# BrushlessMotorController.net
KiCad netlist of a schematic drawn in EAGLE
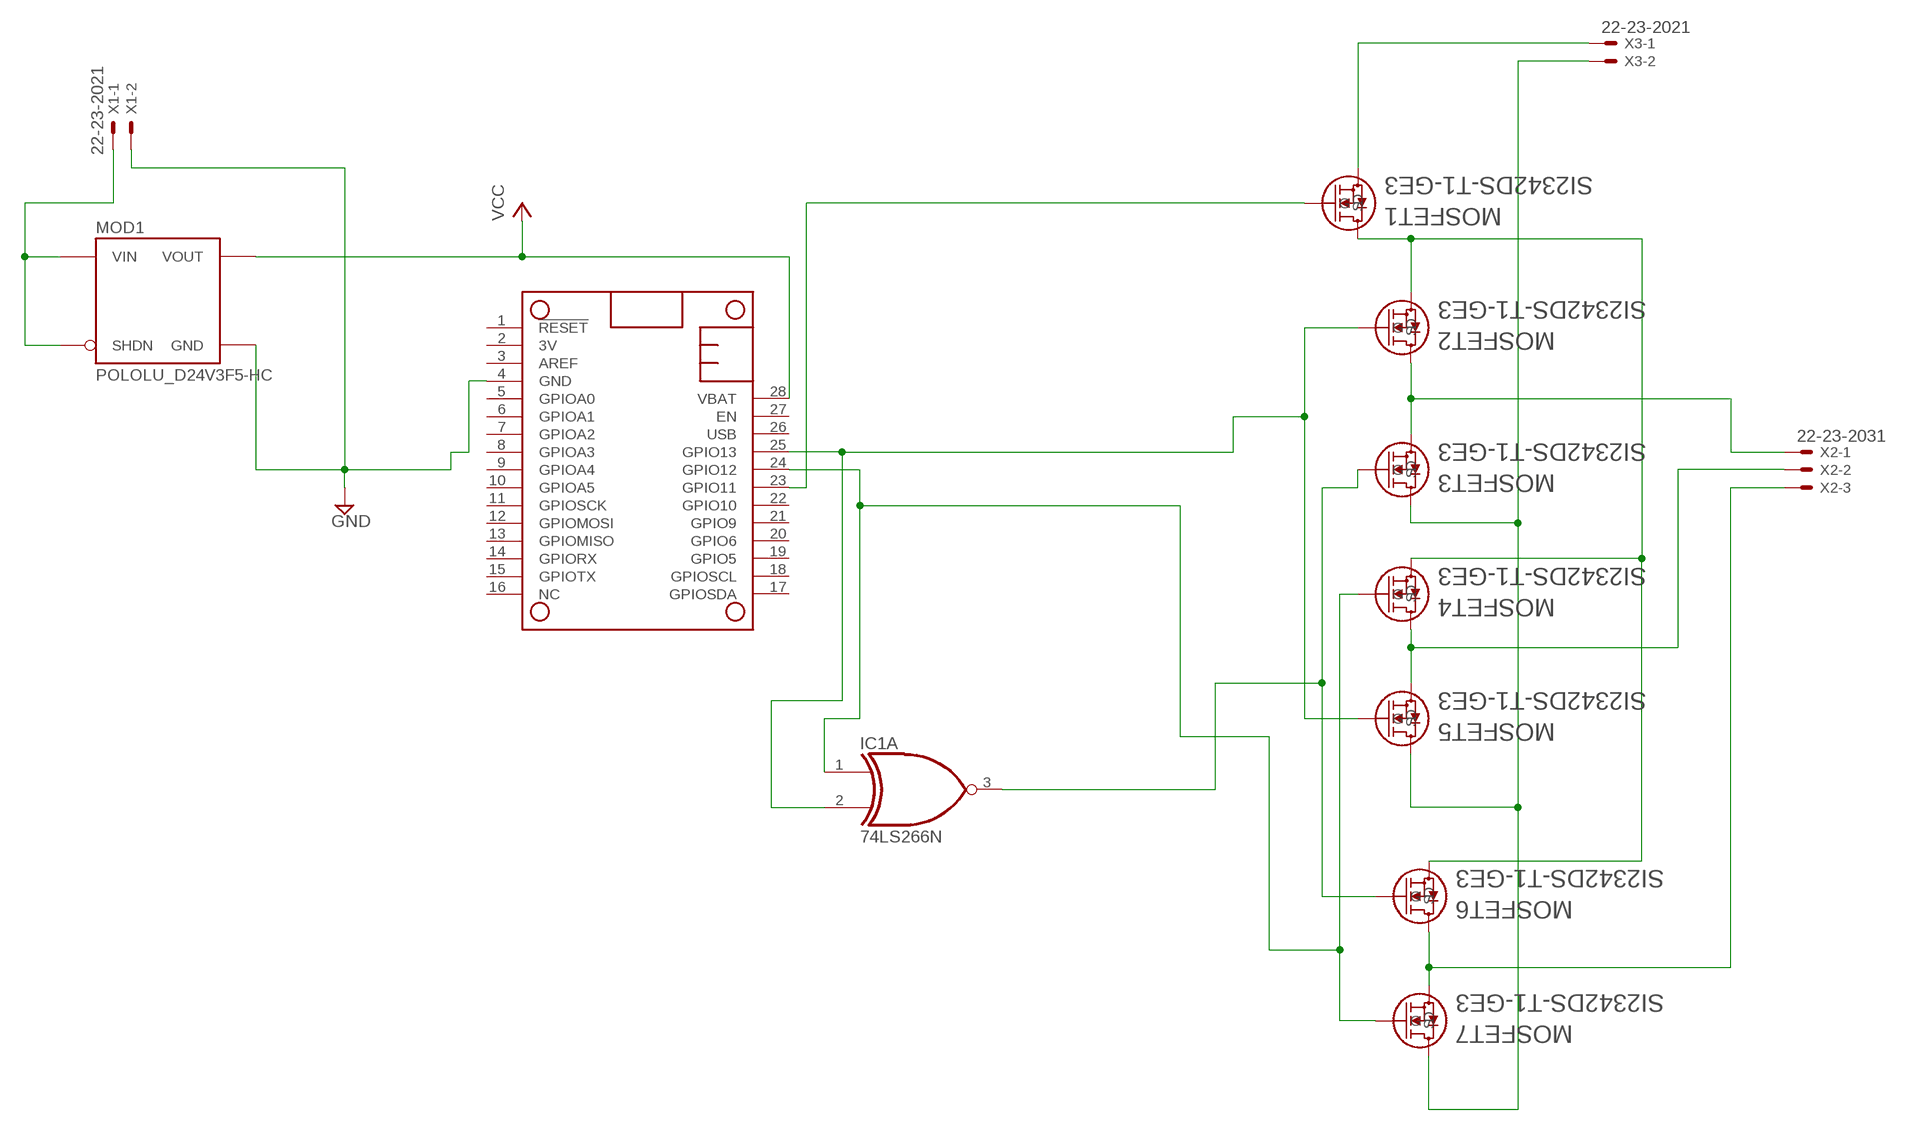
[diagram p0: schematic, sheet 1]

(export (version "E")
  (design (tool "Eeschema 10.0.6"))
  (components
    (comp (ref "IC1")
      (value "74LS266N")
      (footprint "eagle-import:DIL14")
      (libsource (lib "eagle-import") (part "74266NLS"))
    )
    (comp (ref "MOD1")
      (value "POLOLU_D24V3F5-HC")
      (footprint "eagle-import:POLOLU_D24V3F_HC")
      (libsource (lib "eagle-import") (part "POLOLU_D24V3F-HC5"))
    )
    (comp (ref "MOSFET1")
      (value "SI2342DS-T1-GE3")
      (footprint "eagle-import:SOT-23_TO-236_VIS")
      (fields (field (name "COPYRIGHT") "Copyright (C) 2018 Accelerated Designs. All rights reserved"))
      (libsource (lib "eagle-import") (part "SI2342DS-T1-GE3"))
    )
    (comp (ref "MOSFET2")
      (value "SI2342DS-T1-GE3")
      (footprint "eagle-import:SOT-23_TO-236_VIS")
      (fields (field (name "COPYRIGHT") "Copyright (C) 2018 Accelerated Designs. All rights reserved"))
      (libsource (lib "eagle-import") (part "SI2342DS-T1-GE3"))
    )
    (comp (ref "MOSFET3")
      (value "SI2342DS-T1-GE3")
      (footprint "eagle-import:SOT-23_TO-236_VIS")
      (fields (field (name "COPYRIGHT") "Copyright (C) 2018 Accelerated Designs. All rights reserved"))
      (libsource (lib "eagle-import") (part "SI2342DS-T1-GE3"))
    )
    (comp (ref "MOSFET4")
      (value "SI2342DS-T1-GE3")
      (footprint "eagle-import:SOT-23_TO-236_VIS")
      (fields (field (name "COPYRIGHT") "Copyright (C) 2018 Accelerated Designs. All rights reserved"))
      (libsource (lib "eagle-import") (part "SI2342DS-T1-GE3"))
    )
    (comp (ref "MOSFET5")
      (value "SI2342DS-T1-GE3")
      (footprint "eagle-import:SOT-23_TO-236_VIS")
      (fields (field (name "COPYRIGHT") "Copyright (C) 2018 Accelerated Designs. All rights reserved"))
      (libsource (lib "eagle-import") (part "SI2342DS-T1-GE3"))
    )
    (comp (ref "MOSFET6")
      (value "SI2342DS-T1-GE3")
      (footprint "eagle-import:SOT-23_TO-236_VIS")
      (fields (field (name "COPYRIGHT") "Copyright (C) 2018 Accelerated Designs. All rights reserved"))
      (libsource (lib "eagle-import") (part "SI2342DS-T1-GE3"))
    )
    (comp (ref "MOSFET7")
      (value "SI2342DS-T1-GE3")
      (footprint "eagle-import:SOT-23_TO-236_VIS")
      (fields (field (name "COPYRIGHT") "Copyright (C) 2018 Accelerated Designs. All rights reserved"))
      (libsource (lib "eagle-import") (part "SI2342DS-T1-GE3"))
    )
    (comp (ref "MS2")
      (value "FEATHERWING_NODIM")
      (footprint "eagle-import:FEATHERWING_DIM")
      (libsource (lib "eagle-import") (part "FEATHERWING_NODIM"))
    )
    (comp (ref "X1")
      (value "22-23-2021")
      (footprint "eagle-import:22-23-2021")
      (fields (field (name "MF") "MOLEX"))
      (libsource (lib "eagle-import") (part "22-23-2021"))
    )
    (comp (ref "X2")
      (value "22-23-2031")
      (footprint "eagle-import:22-23-2031")
      (fields (field (name "MF") "MOLEX"))
      (libsource (lib "eagle-import") (part "22-23-2031"))
    )
    (comp (ref "X3")
      (value "22-23-2021")
      (footprint "eagle-import:22-23-2021")
      (fields (field (name "MF") "MOLEX"))
      (libsource (lib "eagle-import") (part "22-23-2021"))
    )
  )
  (nets
    (net (code "1") (name "/3V") (class "Default")
      (node (ref "MS2") (pin "2") (pinfunction "3V_2") (pintype "power_in"))
    )
    (net (code "2") (name "/USB") (class "Default")
      (node (ref "MS2") (pin "26") (pinfunction "USB_26") (pintype "power_in"))
    )
    (net (code "3") (name "GND") (class "Default")
      (node (ref "MOD1") (pin "G") (pinfunction "GND_G") (pintype "power_in"))
      (node (ref "MS2") (pin "4") (pinfunction "GND_4") (pintype "power_in"))
      (node (ref "X1") (pin "2") (pinfunction "S_2") (pintype "passive"))
    )
    (net (code "4") (name "Net-(IC1A-I0)") (class "Default")
      (node (ref "IC1") (pin "1") (pinfunction "I0_1") (pintype "input"))
      (node (ref "MOSFET4") (pin "1") (pinfunction "G_1") (pintype "passive"))
      (node (ref "MOSFET7") (pin "1") (pinfunction "G_1") (pintype "passive"))
      (node (ref "MS2") (pin "24") (pinfunction "GPIO12_24") (pintype "bidirectional"))
    )
    (net (code "5") (name "Net-(IC1A-I1)") (class "Default")
      (node (ref "IC1") (pin "2") (pinfunction "I1_2") (pintype "input"))
      (node (ref "MOSFET2") (pin "1") (pinfunction "G_1") (pintype "passive"))
      (node (ref "MOSFET5") (pin "1") (pinfunction "G_1") (pintype "passive"))
      (node (ref "MS2") (pin "25") (pinfunction "GPIO13_25") (pintype "bidirectional"))
    )
    (net (code "6") (name "Net-(IC1A-O)") (class "Default")
      (node (ref "IC1") (pin "3") (pinfunction "O_3") (pintype "open_collector"))
      (node (ref "MOSFET3") (pin "1") (pinfunction "G_1") (pintype "passive"))
      (node (ref "MOSFET6") (pin "1") (pinfunction "G_1") (pintype "passive"))
    )
    (net (code "7") (name "Net-(MOD1-SHDN)") (class "Default")
      (node (ref "MOD1") (pin "I") (pinfunction "VIN_I") (pintype "power_in"))
      (node (ref "MOD1") (pin "S") (pinfunction "SHDN_S") (pintype "input"))
      (node (ref "X1") (pin "1") (pinfunction "S_1") (pintype "passive"))
    )
    (net (code "8") (name "Net-(MOSFET1-D)") (class "Default")
      (node (ref "MOSFET1") (pin "3") (pinfunction "D_3") (pintype "passive"))
      (node (ref "MOSFET2") (pin "2") (pinfunction "S_2") (pintype "passive"))
      (node (ref "MOSFET4") (pin "2") (pinfunction "S_2") (pintype "passive"))
      (node (ref "MOSFET6") (pin "2") (pinfunction "S_2") (pintype "passive"))
    )
    (net (code "9") (name "Net-(MOSFET1-G)") (class "Default")
      (node (ref "MOSFET1") (pin "1") (pinfunction "G_1") (pintype "passive"))
      (node (ref "MS2") (pin "23") (pinfunction "GPIO11_23") (pintype "bidirectional"))
    )
    (net (code "10") (name "Net-(MOSFET1-S)") (class "Default")
      (node (ref "MOSFET1") (pin "2") (pinfunction "S_2") (pintype "passive"))
      (node (ref "X3") (pin "1") (pinfunction "S_1") (pintype "passive"))
    )
    (net (code "11") (name "Net-(MOSFET2-D)") (class "Default")
      (node (ref "MOSFET2") (pin "3") (pinfunction "D_3") (pintype "passive"))
      (node (ref "MOSFET3") (pin "2") (pinfunction "S_2") (pintype "passive"))
      (node (ref "X2") (pin "1") (pinfunction "S_1") (pintype "passive"))
    )
    (net (code "12") (name "Net-(MOSFET3-D)") (class "Default")
      (node (ref "MOSFET3") (pin "3") (pinfunction "D_3") (pintype "passive"))
      (node (ref "MOSFET5") (pin "3") (pinfunction "D_3") (pintype "passive"))
      (node (ref "MOSFET7") (pin "3") (pinfunction "D_3") (pintype "passive"))
      (node (ref "X3") (pin "2") (pinfunction "S_2") (pintype "passive"))
    )
    (net (code "13") (name "Net-(MOSFET4-D)") (class "Default")
      (node (ref "MOSFET4") (pin "3") (pinfunction "D_3") (pintype "passive"))
      (node (ref "MOSFET5") (pin "2") (pinfunction "S_2") (pintype "passive"))
      (node (ref "X2") (pin "2") (pinfunction "S_2") (pintype "passive"))
    )
    (net (code "14") (name "Net-(MOSFET6-D)") (class "Default")
      (node (ref "MOSFET6") (pin "3") (pinfunction "D_3") (pintype "passive"))
      (node (ref "MOSFET7") (pin "2") (pinfunction "S_2") (pintype "passive"))
      (node (ref "X2") (pin "3") (pinfunction "S_3") (pintype "passive"))
    )
    (net (code "15") (name "VCC") (class "Default")
      (node (ref "MOD1") (pin "O") (pinfunction "VOUT_O") (pintype "output"))
      (node (ref "MS2") (pin "28") (pinfunction "VBAT_28") (pintype "power_in"))
    )
    (net (code "16") (name "unconnected-(MS2-AREF-Pad3)") (class "Default")
      (node (ref "MS2") (pin "3") (pinfunction "AREF_3") (pintype "passive"))
    )
    (net (code "17") (name "unconnected-(MS2-EN-Pad27)") (class "Default")
      (node (ref "MS2") (pin "27") (pinfunction "EN_27") (pintype "passive"))
    )
    (net (code "18") (name "unconnected-(MS2-GPIO5-Pad19)") (class "Default")
      (node (ref "MS2") (pin "19") (pinfunction "GPIO5_19") (pintype "bidirectional"))
    )
    (net (code "19") (name "unconnected-(MS2-GPIO6-Pad20)") (class "Default")
      (node (ref "MS2") (pin "20") (pinfunction "GPIO6_20") (pintype "bidirectional"))
    )
    (net (code "20") (name "unconnected-(MS2-GPIO9-Pad21)") (class "Default")
      (node (ref "MS2") (pin "21") (pinfunction "GPIO9_21") (pintype "bidirectional"))
    )
    (net (code "21") (name "unconnected-(MS2-GPIO10-Pad22)") (class "Default")
      (node (ref "MS2") (pin "22") (pinfunction "GPIO10_22") (pintype "bidirectional"))
    )
    (net (code "22") (name "unconnected-(MS2-GPIOA0-Pad5)") (class "Default")
      (node (ref "MS2") (pin "5") (pinfunction "GPIOA0_5") (pintype "bidirectional"))
    )
    (net (code "23") (name "unconnected-(MS2-GPIOA1-Pad6)") (class "Default")
      (node (ref "MS2") (pin "6") (pinfunction "GPIOA1_6") (pintype "bidirectional"))
    )
    (net (code "24") (name "unconnected-(MS2-GPIOA2-Pad7)") (class "Default")
      (node (ref "MS2") (pin "7") (pinfunction "GPIOA2_7") (pintype "bidirectional"))
    )
    (net (code "25") (name "unconnected-(MS2-GPIOA3-Pad8)") (class "Default")
      (node (ref "MS2") (pin "8") (pinfunction "GPIOA3_8") (pintype "bidirectional"))
    )
    (net (code "26") (name "unconnected-(MS2-GPIOA4-Pad9)") (class "Default")
      (node (ref "MS2") (pin "9") (pinfunction "GPIOA4_9") (pintype "bidirectional"))
    )
    (net (code "27") (name "unconnected-(MS2-GPIOA5-Pad10)") (class "Default")
      (node (ref "MS2") (pin "10") (pinfunction "GPIOA5_10") (pintype "bidirectional"))
    )
    (net (code "28") (name "unconnected-(MS2-GPIOMISO-Pad13)") (class "Default")
      (node (ref "MS2") (pin "13") (pinfunction "GPIOMISO_13") (pintype "bidirectional"))
    )
    (net (code "29") (name "unconnected-(MS2-GPIOMOSI-Pad12)") (class "Default")
      (node (ref "MS2") (pin "12") (pinfunction "GPIOMOSI_12") (pintype "bidirectional"))
    )
    (net (code "30") (name "unconnected-(MS2-GPIORX-Pad14)") (class "Default")
      (node (ref "MS2") (pin "14") (pinfunction "GPIORX_14") (pintype "bidirectional"))
    )
    (net (code "31") (name "unconnected-(MS2-GPIOSCK-Pad11)") (class "Default")
      (node (ref "MS2") (pin "11") (pinfunction "GPIOSCK_11") (pintype "bidirectional"))
    )
    (net (code "32") (name "unconnected-(MS2-GPIOSCL-Pad18)") (class "Default")
      (node (ref "MS2") (pin "18") (pinfunction "GPIOSCL_18") (pintype "bidirectional"))
    )
    (net (code "33") (name "unconnected-(MS2-GPIOSDA-Pad17)") (class "Default")
      (node (ref "MS2") (pin "17") (pinfunction "GPIOSDA_17") (pintype "bidirectional"))
    )
    (net (code "34") (name "unconnected-(MS2-GPIOTX-Pad15)") (class "Default")
      (node (ref "MS2") (pin "15") (pinfunction "GPIOTX_15") (pintype "bidirectional"))
    )
    (net (code "35") (name "unconnected-(MS2-NC-Pad16)") (class "Default")
      (node (ref "MS2") (pin "16") (pinfunction "NC_16") (pintype "passive"))
    )
    (net (code "36") (name "unconnected-(MS2-~{RESET}-Pad1)") (class "Default")
      (node (ref "MS2") (pin "1") (pinfunction "~{RESET}_1") (pintype "input"))
    )
  )
)
